# V1_0.net
KiCad netlist of a schematic drawn in Altium Designer
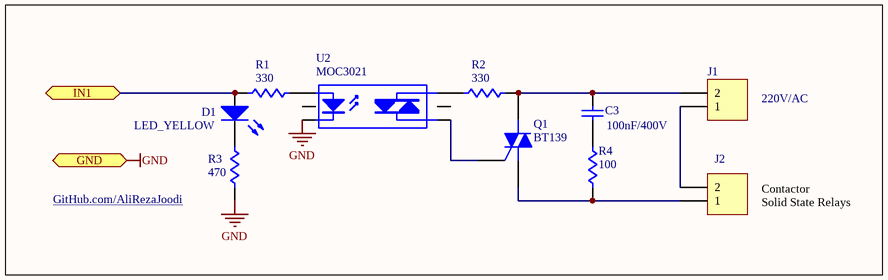
[diagram p0: V1.0.SchDoc]

(export (version "E")
  (design (tool "Eeschema 10.0.6"))
  (components
    (comp (ref "C3")
      (value "100nF/400V")
      (footprint "CAPR7.62-6.8x5")
      (description "Capacitor")
      (fields (field (name "MANUFACTURER") "Generic Components") (field (name "PUBLISHER") "Altium Limited"))
      (libsource (lib "Miscellaneous Devices") (part "Cap"))
    )
    (comp (ref "D1")
      (value "LED_YELLOW")
      (footprint "LED-5mm_Red")
      (description "Typical INFRARED GaAs LED")
      (fields (field (name "MANUFACTURER") "Generic Components") (field (name "PUBLISHER") "Altium Limited"))
      (libsource (lib "Miscellaneous Devices") (part "LED"))
    )
    (comp (ref "J1")
      (value "2PIN")
      (footprint "Fonics_2PIN_1")
      (description "Header, 2-Pin")
      (fields (field (name "PUBLISHER") "Altium Limited"))
      (libsource (lib "Miscellaneous Connectors") (part "Header 2"))
    )
    (comp (ref "J2")
      (value "2PIN")
      (footprint "Fonics_2PIN_1")
      (description "Header, 2-Pin")
      (fields (field (name "PUBLISHER") "Altium Limited"))
      (libsource (lib "Miscellaneous Connectors") (part "Header 2"))
    )
    (comp (ref "Q1")
      (value "BT139")
      (footprint "TO220V")
      (description "Silicon Bidirectional Triode Thyristor")
      (fields (field (name "MANUFACTURER") "Generic Components") (field (name "PUBLISHER") "Altium Limited"))
      (libsource (lib "Miscellaneous Devices") (part "Triac"))
    )
    (comp (ref "R1")
      (value "330")
      (footprint "AXIAL-0.4")
      (description "Resistor")
      (fields (field (name "MANUFACTURER") "Generic Components") (field (name "PUBLISHER") "Altium Limited"))
      (libsource (lib "Miscellaneous Devices") (part "Res1"))
    )
    (comp (ref "R2")
      (value "330")
      (footprint "AXIAL-0.4")
      (description "Resistor")
      (fields (field (name "MANUFACTURER") "Generic Components") (field (name "PUBLISHER") "Altium Limited"))
      (libsource (lib "Miscellaneous Devices") (part "Res1"))
    )
    (comp (ref "R3")
      (value "470")
      (footprint "AXIAL-0.4")
      (description "Resistor")
      (fields (field (name "MANUFACTURER") "Generic Components") (field (name "PUBLISHER") "Altium Limited"))
      (libsource (lib "Miscellaneous Devices") (part "Res1"))
    )
    (comp (ref "R4")
      (value "100")
      (footprint "AXIAL-0.4")
      (description "Resistor")
      (fields (field (name "MANUFACTURER") "Generic Components") (field (name "PUBLISHER") "Altium Limited"))
      (libsource (lib "Miscellaneous Devices") (part "Res1"))
    )
    (comp (ref "U2")
      (value "MOC3021")
      (footprint "DIP-6")
      (description "Opto-Triac")
      (fields
        (field (name "PUBLISHER") "www.picpars.com")
        (field (name "DESIGNER") "Seyed Mohsen Ghasemian")
        (field (name "E-MAIL") "picpars@gmail.com")
      )
      (libsource (lib "PicPars.com_usefully_Library") (part "MOC3021-3"))
    )
  )
  (nets
    (net (code "1") (name "/IN1") (class "Default")
      (node (ref "D1") (pin "1") (pinfunction "A_1") (pintype "passive"))
      (node (ref "R1") (pin "1") (pinfunction "1_1") (pintype "passive"))
    )
    (net (code "2") (name "GND") (class "Default")
      (node (ref "R3") (pin "2") (pinfunction "2_2") (pintype "passive"))
      (node (ref "U2") (pin "2") (pinfunction "K_2") (pintype "passive"))
    )
    (net (code "3") (name "Net-(C3-Pad1)") (class "Default")
      (node (ref "C3") (pin "1") (pinfunction "1_1") (pintype "passive"))
      (node (ref "R4") (pin "2") (pinfunction "2_2") (pintype "passive"))
    )
    (net (code "4") (name "Net-(D1-K)") (class "Default")
      (node (ref "D1") (pin "2") (pinfunction "K_2") (pintype "passive"))
      (node (ref "R3") (pin "1") (pinfunction "1_1") (pintype "passive"))
    )
    (net (code "5") (name "Net-(J1-Pad1)") (class "Default")
      (node (ref "J1") (pin "1") (pinfunction "1_1") (pintype "passive"))
      (node (ref "J2") (pin "2") (pinfunction "2_2") (pintype "passive"))
    )
    (net (code "6") (name "Net-(Q1-G)") (class "Default")
      (node (ref "Q1") (pin "3") (pinfunction "G_3") (pintype "passive"))
      (node (ref "U2") (pin "6") (pinfunction "A/K_6") (pintype "passive"))
    )
    (net (code "7") (name "Net-(Q1-M1)") (class "Default")
      (node (ref "J2") (pin "1") (pinfunction "1_1") (pintype "passive"))
      (node (ref "Q1") (pin "1") (pinfunction "M1_1") (pintype "passive"))
      (node (ref "R4") (pin "1") (pinfunction "1_1") (pintype "passive"))
    )
    (net (code "8") (name "Net-(Q1-M2)") (class "Default")
      (node (ref "C3") (pin "2") (pinfunction "2_2") (pintype "passive"))
      (node (ref "J1") (pin "2") (pinfunction "2_2") (pintype "passive"))
      (node (ref "Q1") (pin "2") (pinfunction "M2_2") (pintype "passive"))
      (node (ref "R2") (pin "2") (pinfunction "2_2") (pintype "passive"))
    )
    (net (code "9") (name "Net-(R2-Pad1)") (class "Default")
      (node (ref "R2") (pin "1") (pinfunction "1_1") (pintype "passive"))
      (node (ref "U2") (pin "4") (pinfunction "A/K_4") (pintype "passive"))
    )
    (net (code "10") (name "Net-(U2-A)") (class "Default")
      (node (ref "R1") (pin "2") (pinfunction "2_2") (pintype "passive"))
      (node (ref "U2") (pin "1") (pinfunction "A_1") (pintype "passive"))
    )
    (net (code "11") (name "unconnected-(U2-NC-Pad3)") (class "Default")
      (node (ref "U2") (pin "3") (pinfunction "NC_3") (pintype "passive"))
    )
    (net (code "12") (name "unconnected-(U2-NC-Pad5)") (class "Default")
      (node (ref "U2") (pin "5") (pinfunction "NC_5") (pintype "passive"))
    )
  )
)
